# Connectors.net
KiCad netlist of a schematic drawn in Altium Designer
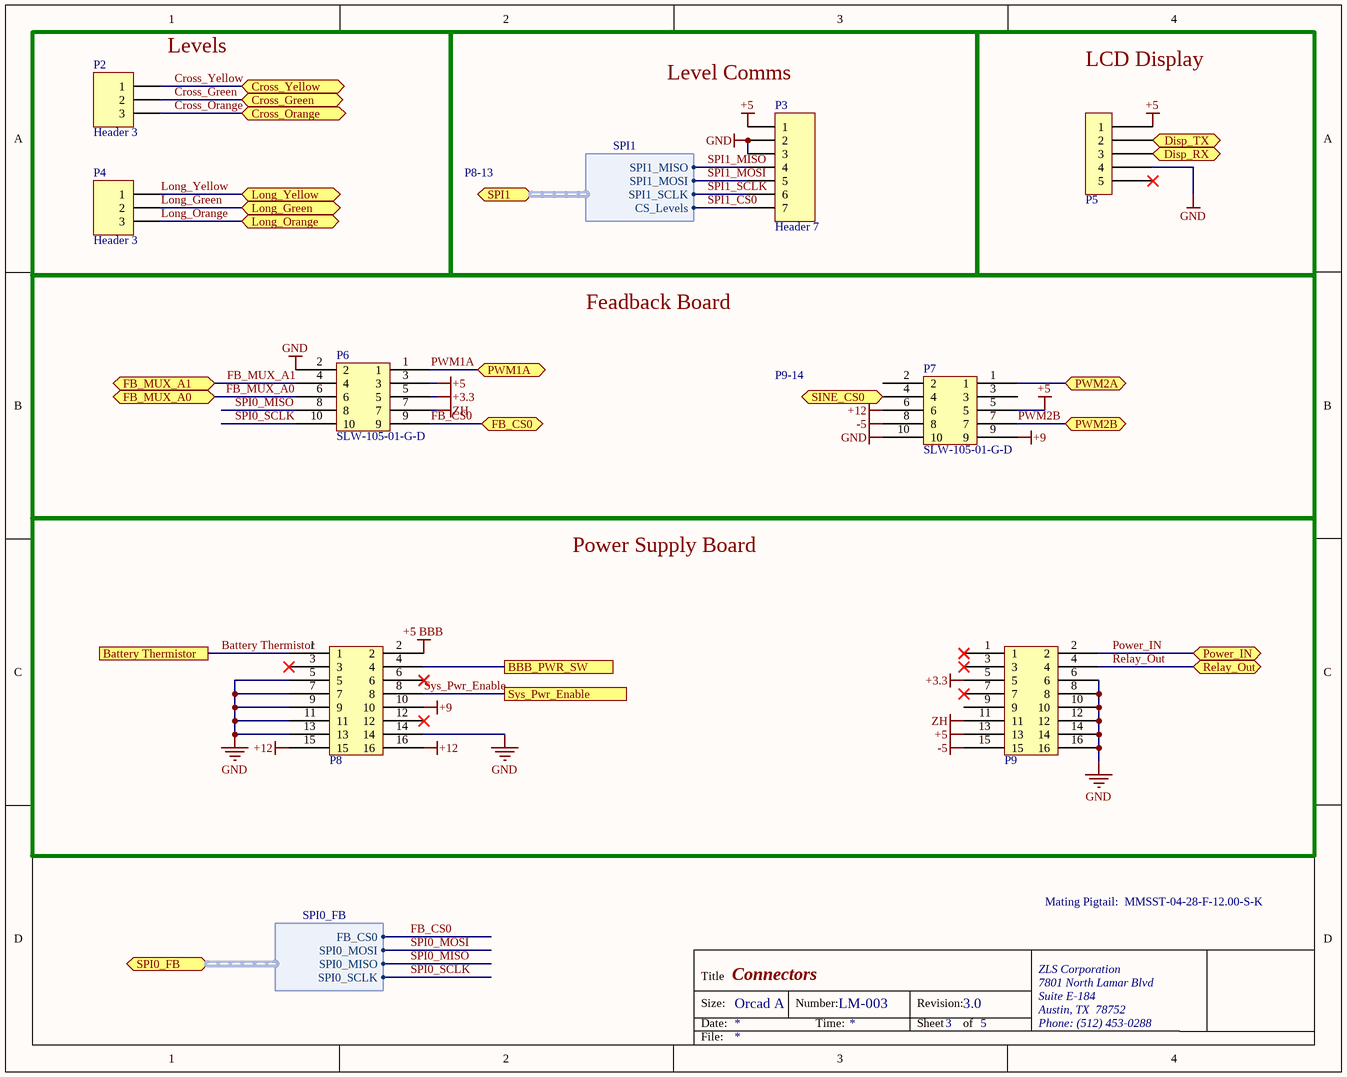
[diagram p0: Connectors.SchDoc]

(export (version "E")
  (design (tool "Eeschema 10.0.6"))
  (components
    (comp (ref "P2")
      (value "Header 3")
      (footprint "HDR1X3")
      (description "Header, 3-Pin")
      (fields (field (name "PUBLISHER") "Altium Limited"))
      (libsource (lib "Miscellaneous Connectors") (part "Header 3"))
    )
    (comp (ref "P3")
      (value "Header 7")
      (footprint "HDR1X7")
      (description "Header, 7-Pin")
      (fields (field (name "PUBLISHER") "Altium Limited"))
      (libsource (lib "Miscellaneous Connectors") (part "Header 7"))
    )
    (comp (ref "P4")
      (value "Header 3")
      (footprint "HDR1X3")
      (description "Header, 3-Pin")
      (fields (field (name "PUBLISHER") "Altium Limited"))
      (libsource (lib "Miscellaneous Connectors") (part "Header 3"))
    )
    (comp (ref "P5")
      (value "IPL1-105-01-F-S-K")
      (footprint "IPL1-105-01-F-S-K")
      (libsource (lib "ZLS_Schematic_lib") (part "IPL1-105-01-F-S-K"))
    )
    (comp (ref "P6")
      (value "SLW-105-01-G-D")
      (footprint "SLW-105-01-G-D")
      (description "CONN RCPT .100\" 10POS DUAL GOLD")
      (fields (field (name "MANUFACTURER") "Samtec Inc."))
      (libsource (lib "ZLS_Schematic_lib") (part "SLW-105-01-G-D"))
    )
    (comp (ref "P7")
      (value "SLW-105-01-G-D")
      (footprint "SLW-105-01-G-D")
      (description "CONN RCPT .100\" 10POS DUAL GOLD")
      (fields (field (name "MANUFACTURER") "Samtec Inc."))
      (libsource (lib "ZLS_Schematic_lib") (part "SLW-105-01-G-D"))
    )
    (comp (ref "P8")
      (value "SLW-108-01-G-D")
      (footprint "SLW-108-01-G-D")
      (libsource (lib "ZLS_Schematic_lib") (part "SLW-108-01-G-D"))
    )
    (comp (ref "P9")
      (value "SLW-108-01-G-D")
      (footprint "SLW-108-01-G-D")
      (libsource (lib "ZLS_Schematic_lib") (part "SLW-108-01-G-D"))
    )
  )
  (nets
    (net (code "3") (name "+3.3") (class "Default")
      (node (ref "P6") (pin "5") (pinfunction "5_5") (pintype "passive"))
      (node (ref "P9") (pin "5") (pinfunction "5_5") (pintype "passive"))
    )
    (net (code "4") (name "+5") (class "Default")
      (node (ref "P3") (pin "1") (pinfunction "1_1") (pintype "passive"))
      (node (ref "P5") (pin "1") (pinfunction "1_1") (pintype "passive"))
      (node (ref "P6") (pin "3") (pinfunction "3_3") (pintype "passive"))
      (node (ref "P7") (pin "5") (pinfunction "5_5") (pintype "passive"))
      (node (ref "P9") (pin "13") (pinfunction "13_13") (pintype "passive"))
    )
    (net (code "5") (name "+5 BBB") (class "Default")
      (node (ref "P8") (pin "2") (pinfunction "2_2") (pintype "passive"))
    )
    (net (code "6") (name "+9") (class "Default")
      (node (ref "P7") (pin "9") (pinfunction "9_9") (pintype "passive"))
      (node (ref "P8") (pin "10") (pinfunction "10_10") (pintype "passive"))
    )
    (net (code "7") (name "+12") (class "Default")
      (node (ref "P7") (pin "6") (pinfunction "6_6") (pintype "passive"))
      (node (ref "P8") (pin "15") (pinfunction "15_15") (pintype "passive"))
      (node (ref "P8") (pin "16") (pinfunction "16_16") (pintype "passive"))
    )
    (net (code "8") (name "-5") (class "Default")
      (node (ref "P7") (pin "8") (pinfunction "8_8") (pintype "passive"))
      (node (ref "P9") (pin "15") (pinfunction "15_15") (pintype "passive"))
    )
    (net (code "9") (name "/BBB_PWR_SW") (class "Default")
      (node (ref "P8") (pin "4") (pinfunction "4_4") (pintype "passive"))
    )
    (net (code "10") (name "/Battery Thermistor") (class "Default")
      (node (ref "P8") (pin "1") (pinfunction "1_1") (pintype "passive"))
    )
    (net (code "11") (name "/Cross_Green") (class "Default")
      (node (ref "P2") (pin "2") (pinfunction "2_2") (pintype "passive"))
    )
    (net (code "12") (name "/Cross_Orange") (class "Default")
      (node (ref "P2") (pin "3") (pinfunction "3_3") (pintype "passive"))
    )
    (net (code "13") (name "/Cross_Yellow") (class "Default")
      (node (ref "P2") (pin "1") (pinfunction "1_1") (pintype "passive"))
    )
    (net (code "14") (name "/Disp_RX") (class "Default")
      (node (ref "P5") (pin "3") (pinfunction "3_3") (pintype "passive"))
    )
    (net (code "15") (name "/Disp_TX") (class "Default")
      (node (ref "P5") (pin "2") (pinfunction "2_2") (pintype "passive"))
    )
    (net (code "16") (name "/FB_CS0") (class "Default")
      (node (ref "P6") (pin "9") (pinfunction "9_9") (pintype "passive"))
    )
    (net (code "17") (name "/FB_MUX_A0") (class "Default")
      (node (ref "P6") (pin "6") (pinfunction "6_6") (pintype "passive"))
    )
    (net (code "18") (name "/FB_MUX_A1") (class "Default")
      (node (ref "P6") (pin "4") (pinfunction "4_4") (pintype "passive"))
    )
    (net (code "19") (name "/Long_Green") (class "Default")
      (node (ref "P4") (pin "2") (pinfunction "2_2") (pintype "passive"))
    )
    (net (code "20") (name "/Long_Orange") (class "Default")
      (node (ref "P4") (pin "3") (pinfunction "3_3") (pintype "passive"))
    )
    (net (code "21") (name "/Long_Yellow") (class "Default")
      (node (ref "P4") (pin "1") (pinfunction "1_1") (pintype "passive"))
    )
    (net (code "22") (name "/PWM1A") (class "Default")
      (node (ref "P6") (pin "1") (pinfunction "1_1") (pintype "passive"))
    )
    (net (code "23") (name "/PWM2A") (class "Default")
      (node (ref "P7") (pin "1") (pinfunction "1_1") (pintype "passive"))
    )
    (net (code "24") (name "/PWM2B") (class "Default")
      (node (ref "P7") (pin "7") (pinfunction "7_7") (pintype "passive"))
    )
    (net (code "25") (name "/Power_IN") (class "Default")
      (node (ref "P9") (pin "2") (pinfunction "2_2") (pintype "passive"))
    )
    (net (code "26") (name "/Relay_Out") (class "Default")
      (node (ref "P9") (pin "4") (pinfunction "4_4") (pintype "passive"))
    )
    (net (code "27") (name "/SINE_CS0") (class "Default")
      (node (ref "P7") (pin "4") (pinfunction "4_4") (pintype "passive"))
    )
    (net (code "28") (name "/SPI0_MISO") (class "Default")
      (node (ref "P6") (pin "8") (pinfunction "8_8") (pintype "passive"))
    )
    (net (code "30") (name "/SPI0_SCLK") (class "Default")
      (node (ref "P6") (pin "10") (pinfunction "10_10") (pintype "passive"))
    )
    (net (code "31") (name "/SPI1_CS0") (class "Default")
      (node (ref "P3") (pin "7") (pinfunction "7_7") (pintype "passive"))
    )
    (net (code "32") (name "/SPI1_MISO") (class "Default")
      (node (ref "P3") (pin "4") (pinfunction "4_4") (pintype "passive"))
    )
    (net (code "33") (name "/SPI1_MOSI") (class "Default")
      (node (ref "P3") (pin "5") (pinfunction "5_5") (pintype "passive"))
    )
    (net (code "34") (name "/SPI1_SCLK") (class "Default")
      (node (ref "P3") (pin "6") (pinfunction "6_6") (pintype "passive"))
    )
    (net (code "35") (name "/Sys_Pwr_Enable") (class "Default")
      (node (ref "P8") (pin "8") (pinfunction "8_8") (pintype "passive"))
    )
    (net (code "38") (name "GND") (class "Default")
      (node (ref "P3") (pin "2") (pinfunction "2_2") (pintype "passive"))
      (node (ref "P3") (pin "3") (pinfunction "3_3") (pintype "passive"))
      (node (ref "P5") (pin "4") (pinfunction "4_4") (pintype "passive"))
      (node (ref "P6") (pin "2") (pinfunction "2_2") (pintype "passive"))
      (node (ref "P7") (pin "10") (pinfunction "10_10") (pintype "passive"))
      (node (ref "P8") (pin "11") (pinfunction "11_11") (pintype "passive"))
      (node (ref "P8") (pin "13") (pinfunction "13_13") (pintype "passive"))
      (node (ref "P8") (pin "14") (pinfunction "14_14") (pintype "passive"))
      (node (ref "P8") (pin "5") (pinfunction "5_5") (pintype "passive"))
      (node (ref "P8") (pin "7") (pinfunction "7_7") (pintype "passive"))
      (node (ref "P8") (pin "9") (pinfunction "9_9") (pintype "passive"))
      (node (ref "P9") (pin "10") (pinfunction "10_10") (pintype "passive"))
      (node (ref "P9") (pin "12") (pinfunction "12_12") (pintype "passive"))
      (node (ref "P9") (pin "14") (pinfunction "14_14") (pintype "passive"))
      (node (ref "P9") (pin "16") (pinfunction "16_16") (pintype "passive"))
      (node (ref "P9") (pin "6") (pinfunction "6_6") (pintype "passive"))
      (node (ref "P9") (pin "8") (pinfunction "8_8") (pintype "passive"))
    )
    (net (code "39") (name "ZH") (class "Default")
      (node (ref "P6") (pin "7") (pinfunction "7_7") (pintype "passive"))
      (node (ref "P9") (pin "11") (pinfunction "11_11") (pintype "passive"))
    )
    (net (code "40") (name "unconnected-(P5-Pad5)") (class "Default")
      (node (ref "P5") (pin "5") (pinfunction "5_5") (pintype "passive+no_connect"))
    )
    (net (code "41") (name "unconnected-(P7-Pad2)") (class "Default")
      (node (ref "P7") (pin "2") (pinfunction "2_2") (pintype "passive"))
    )
    (net (code "42") (name "unconnected-(P7-Pad3)") (class "Default")
      (node (ref "P7") (pin "3") (pinfunction "3_3") (pintype "passive"))
    )
    (net (code "43") (name "unconnected-(P8-Pad3)") (class "Default")
      (node (ref "P8") (pin "3") (pinfunction "3_3") (pintype "passive+no_connect"))
    )
    (net (code "44") (name "unconnected-(P8-Pad6)") (class "Default")
      (node (ref "P8") (pin "6") (pinfunction "6_6") (pintype "passive+no_connect"))
    )
    (net (code "45") (name "unconnected-(P8-Pad12)") (class "Default")
      (node (ref "P8") (pin "12") (pinfunction "12_12") (pintype "passive+no_connect"))
    )
    (net (code "46") (name "unconnected-(P9-Pad1)") (class "Default")
      (node (ref "P9") (pin "1") (pinfunction "1_1") (pintype "passive+no_connect"))
    )
    (net (code "47") (name "unconnected-(P9-Pad3)") (class "Default")
      (node (ref "P9") (pin "3") (pinfunction "3_3") (pintype "passive+no_connect"))
    )
    (net (code "48") (name "unconnected-(P9-Pad7)") (class "Default")
      (node (ref "P9") (pin "7") (pinfunction "7_7") (pintype "passive+no_connect"))
    )
    (net (code "49") (name "unconnected-(P9-Pad9)") (class "Default")
      (node (ref "P9") (pin "9") (pinfunction "9_9") (pintype "passive"))
    )
  )
)
